# Power_section.net
KiCad netlist of a schematic drawn in EAGLE
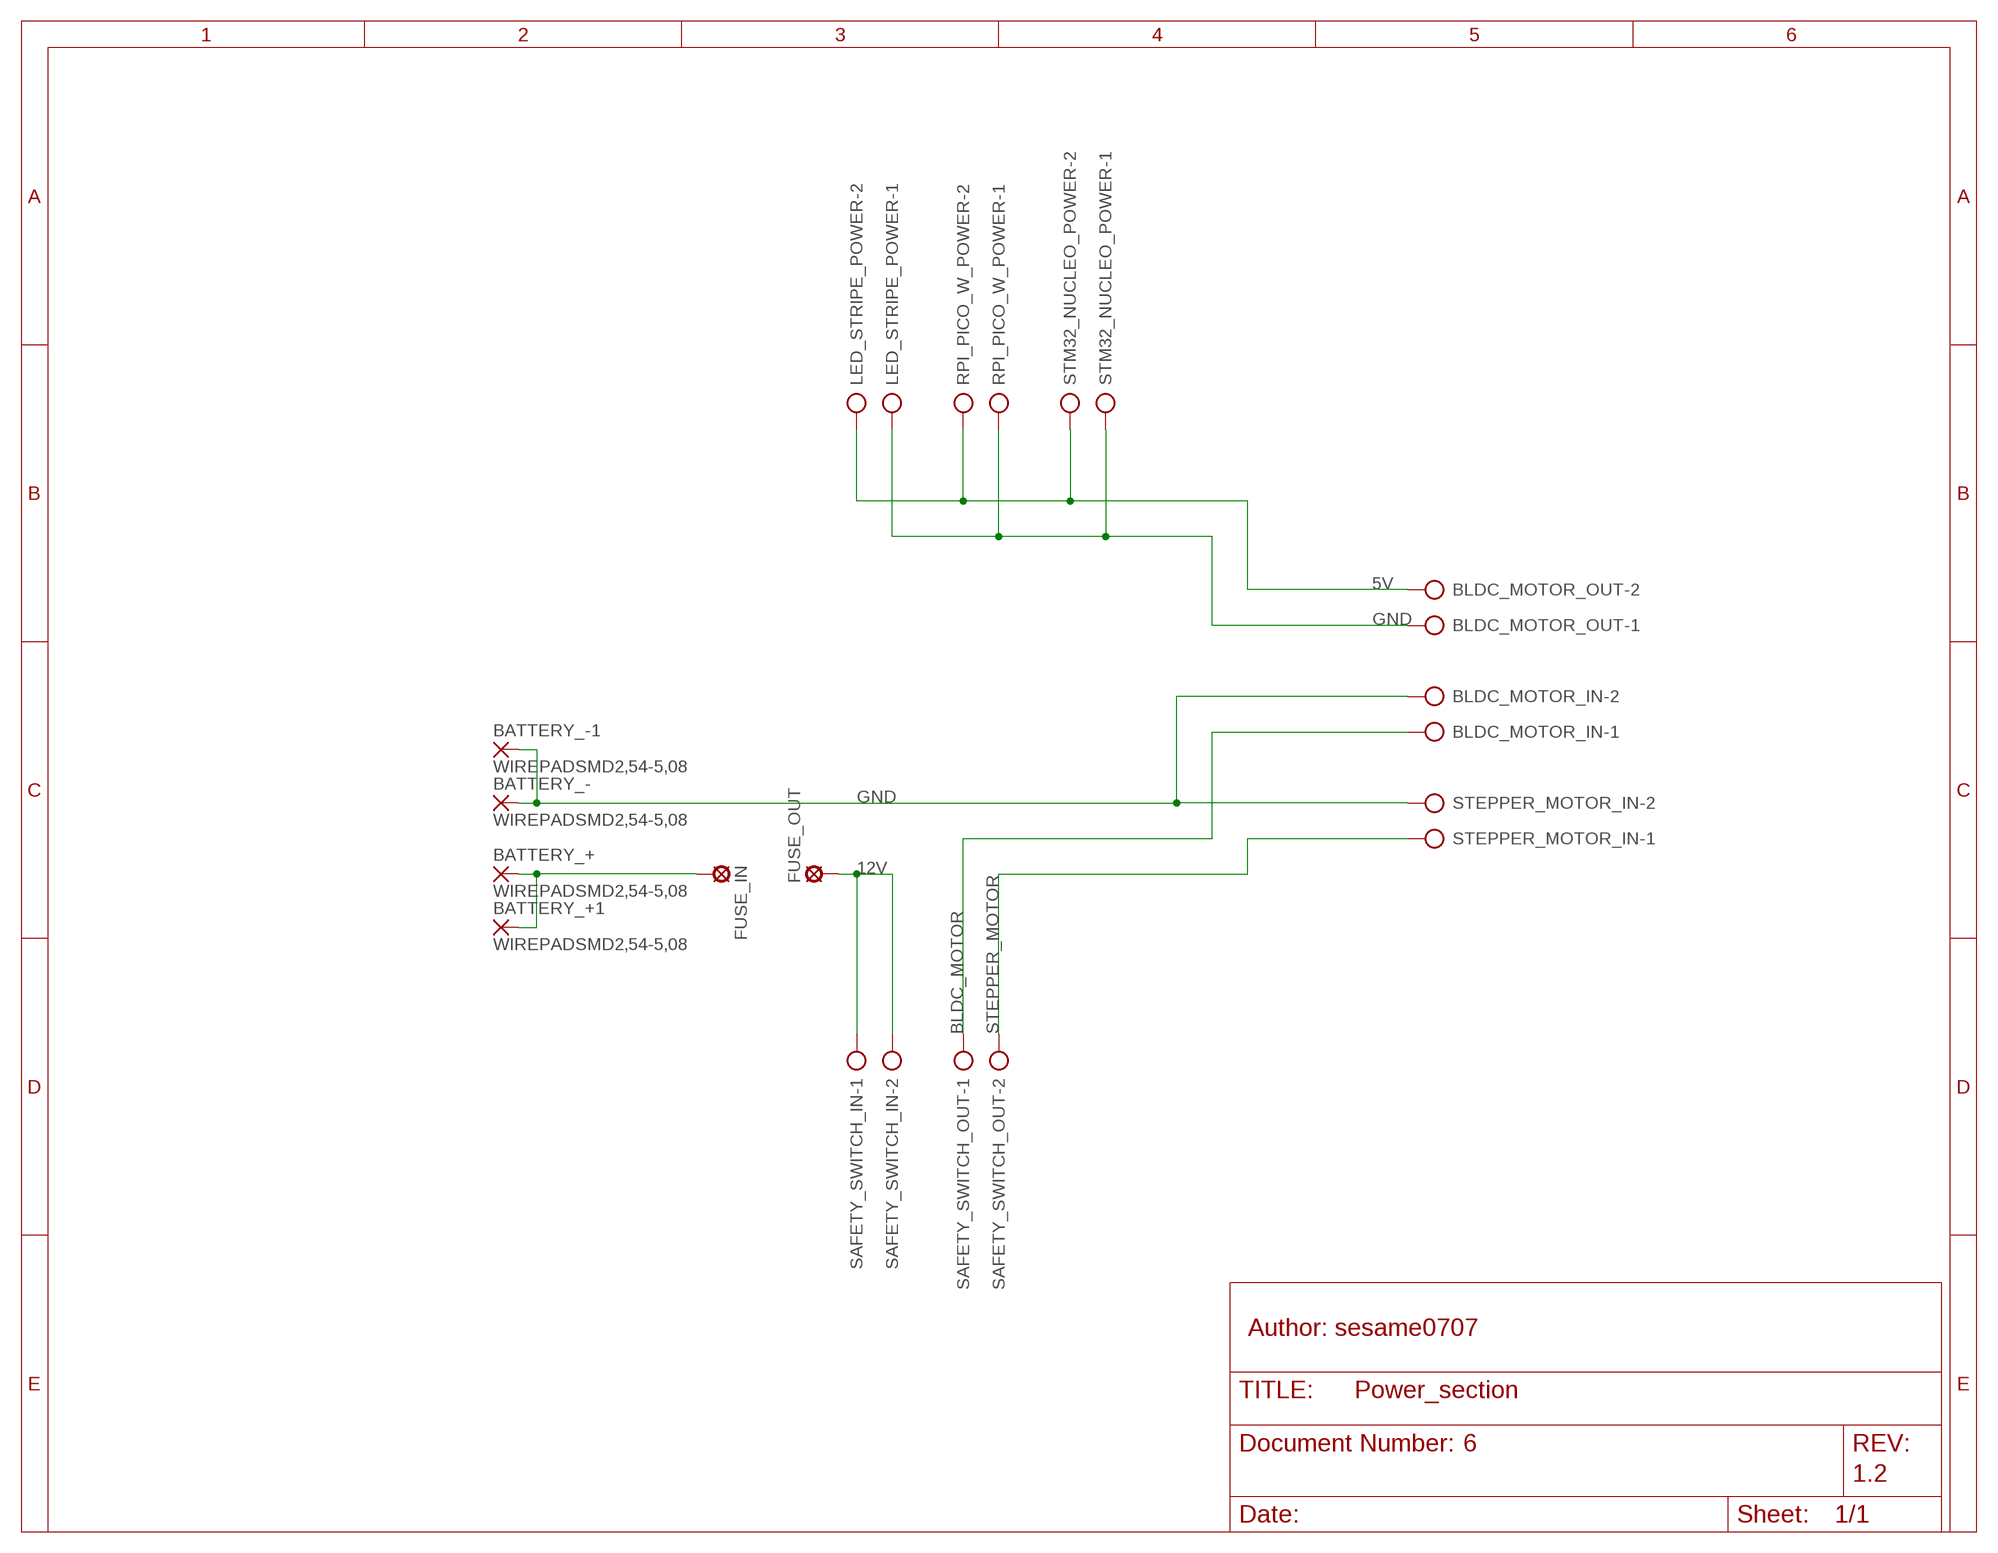
[diagram p0: schematic, sheet 1]

(export (version "E")
  (design (tool "Eeschema 10.0.6"))
  (components
    (comp (ref "BATTERY_+")
      (value "WIREPADSMD2,54-5,08")
      (footprint "eagle-import:SMD2,54-5,08")
      (libsource (lib "eagle-import") (part "WIREPADSMD2,54-5,08"))
    )
    (comp (ref "BATTERY_+1")
      (value "WIREPADSMD2,54-5,08")
      (footprint "eagle-import:SMD2,54-5,08")
      (libsource (lib "eagle-import") (part "WIREPADSMD2,54-5,08"))
    )
    (comp (ref "BATTERY_-")
      (value "WIREPADSMD2,54-5,08")
      (footprint "eagle-import:SMD2,54-5,08")
      (libsource (lib "eagle-import") (part "WIREPADSMD2,54-5,08"))
    )
    (comp (ref "BATTERY_-1")
      (value "WIREPADSMD2,54-5,08")
      (footprint "eagle-import:SMD2,54-5,08")
      (libsource (lib "eagle-import") (part "WIREPADSMD2,54-5,08"))
    )
    (comp (ref "BLDC_MOTOR_IN")
      (value "AK500/2")
      (footprint "eagle-import:AK500_2")
      (libsource (lib "eagle-import") (part "AK500/2"))
    )
    (comp (ref "BLDC_MOTOR_OUT")
      (value "AK500/2")
      (footprint "eagle-import:AK500_2")
      (libsource (lib "eagle-import") (part "AK500/2"))
    )
    (comp (ref "FUSE_IN")
      (value "SE14")
      (footprint "eagle-import:SE14")
      (libsource (lib "eagle-import") (part "SE14"))
    )
    (comp (ref "FUSE_OUT")
      (value "SE14")
      (footprint "eagle-import:SE14")
      (libsource (lib "eagle-import") (part "SE14"))
    )
    (comp (ref "LED_STRIPE_POWER")
      (value "AK500/2")
      (footprint "eagle-import:AK500_2")
      (libsource (lib "eagle-import") (part "AK500/2"))
    )
    (comp (ref "RPI_PICO_W_POWER")
      (value "AK500/2")
      (footprint "eagle-import:AK500_2")
      (libsource (lib "eagle-import") (part "AK500/2"))
    )
    (comp (ref "SAFETY_SWITCH_IN")
      (value "AK500/2")
      (footprint "eagle-import:AK500_2")
      (libsource (lib "eagle-import") (part "AK500/2"))
    )
    (comp (ref "SAFETY_SWITCH_OUT")
      (value "AK500/2")
      (footprint "eagle-import:AK500_2")
      (libsource (lib "eagle-import") (part "AK500/2"))
    )
    (comp (ref "STEPPER_MOTOR_IN")
      (value "AK500/2")
      (footprint "eagle-import:AK500_2")
      (libsource (lib "eagle-import") (part "AK500/2"))
    )
    (comp (ref "STM32_NUCLEO_POWER")
      (value "AK500/2")
      (footprint "eagle-import:AK500_2")
      (libsource (lib "eagle-import") (part "AK500/2"))
    )
  )
  (nets
    (net (code "1") (name "/5V") (class "Default")
      (node (ref "BLDC_MOTOR_OUT") (pin "2") (pinfunction "KL_2") (pintype "passive"))
      (node (ref "LED_STRIPE_POWER") (pin "2") (pinfunction "KL_2") (pintype "passive"))
      (node (ref "RPI_PICO_W_POWER") (pin "2") (pinfunction "KL_2") (pintype "passive"))
      (node (ref "STM32_NUCLEO_POWER") (pin "2") (pinfunction "KL_2") (pintype "passive"))
    )
    (net (code "2") (name "/12V") (class "Default")
      (node (ref "FUSE_OUT") (pin "MP") (pinfunction "MP_MP") (pintype "passive"))
      (node (ref "SAFETY_SWITCH_IN") (pin "1") (pinfunction "KL_1") (pintype "passive"))
      (node (ref "SAFETY_SWITCH_IN") (pin "2") (pinfunction "KL_2") (pintype "passive"))
    )
    (net (code "3") (name "/BLDC_MOTOR") (class "Default")
      (node (ref "BLDC_MOTOR_IN") (pin "1") (pinfunction "KL_1") (pintype "passive"))
      (node (ref "SAFETY_SWITCH_OUT") (pin "1") (pinfunction "KL_1") (pintype "passive"))
    )
    (net (code "4") (name "/GND") (class "Default")
      (node (ref "BATTERY_-") (pin "1") (pinfunction "P_1") (pintype "passive"))
      (node (ref "BATTERY_-1") (pin "1") (pinfunction "P_1") (pintype "passive"))
      (node (ref "BLDC_MOTOR_IN") (pin "2") (pinfunction "KL_2") (pintype "passive"))
      (node (ref "BLDC_MOTOR_OUT") (pin "1") (pinfunction "KL_1") (pintype "passive"))
      (node (ref "LED_STRIPE_POWER") (pin "1") (pinfunction "KL_1") (pintype "passive"))
      (node (ref "RPI_PICO_W_POWER") (pin "1") (pinfunction "KL_1") (pintype "passive"))
      (node (ref "STEPPER_MOTOR_IN") (pin "2") (pinfunction "KL_2") (pintype "passive"))
      (node (ref "STM32_NUCLEO_POWER") (pin "1") (pinfunction "KL_1") (pintype "passive"))
    )
    (net (code "5") (name "/STEPPER_MOTOR") (class "Default")
      (node (ref "SAFETY_SWITCH_OUT") (pin "2") (pinfunction "KL_2") (pintype "passive"))
      (node (ref "STEPPER_MOTOR_IN") (pin "1") (pinfunction "KL_1") (pintype "passive"))
    )
    (net (code "6") (name "Net-(BATTERY_+-P)") (class "Default")
      (node (ref "BATTERY_+") (pin "1") (pinfunction "P_1") (pintype "passive"))
      (node (ref "BATTERY_+1") (pin "1") (pinfunction "P_1") (pintype "passive"))
      (node (ref "FUSE_IN") (pin "MP") (pinfunction "MP_MP") (pintype "passive"))
    )
  )
)
